# POWER.net
KiCad netlist of a schematic drawn in Altium Designer
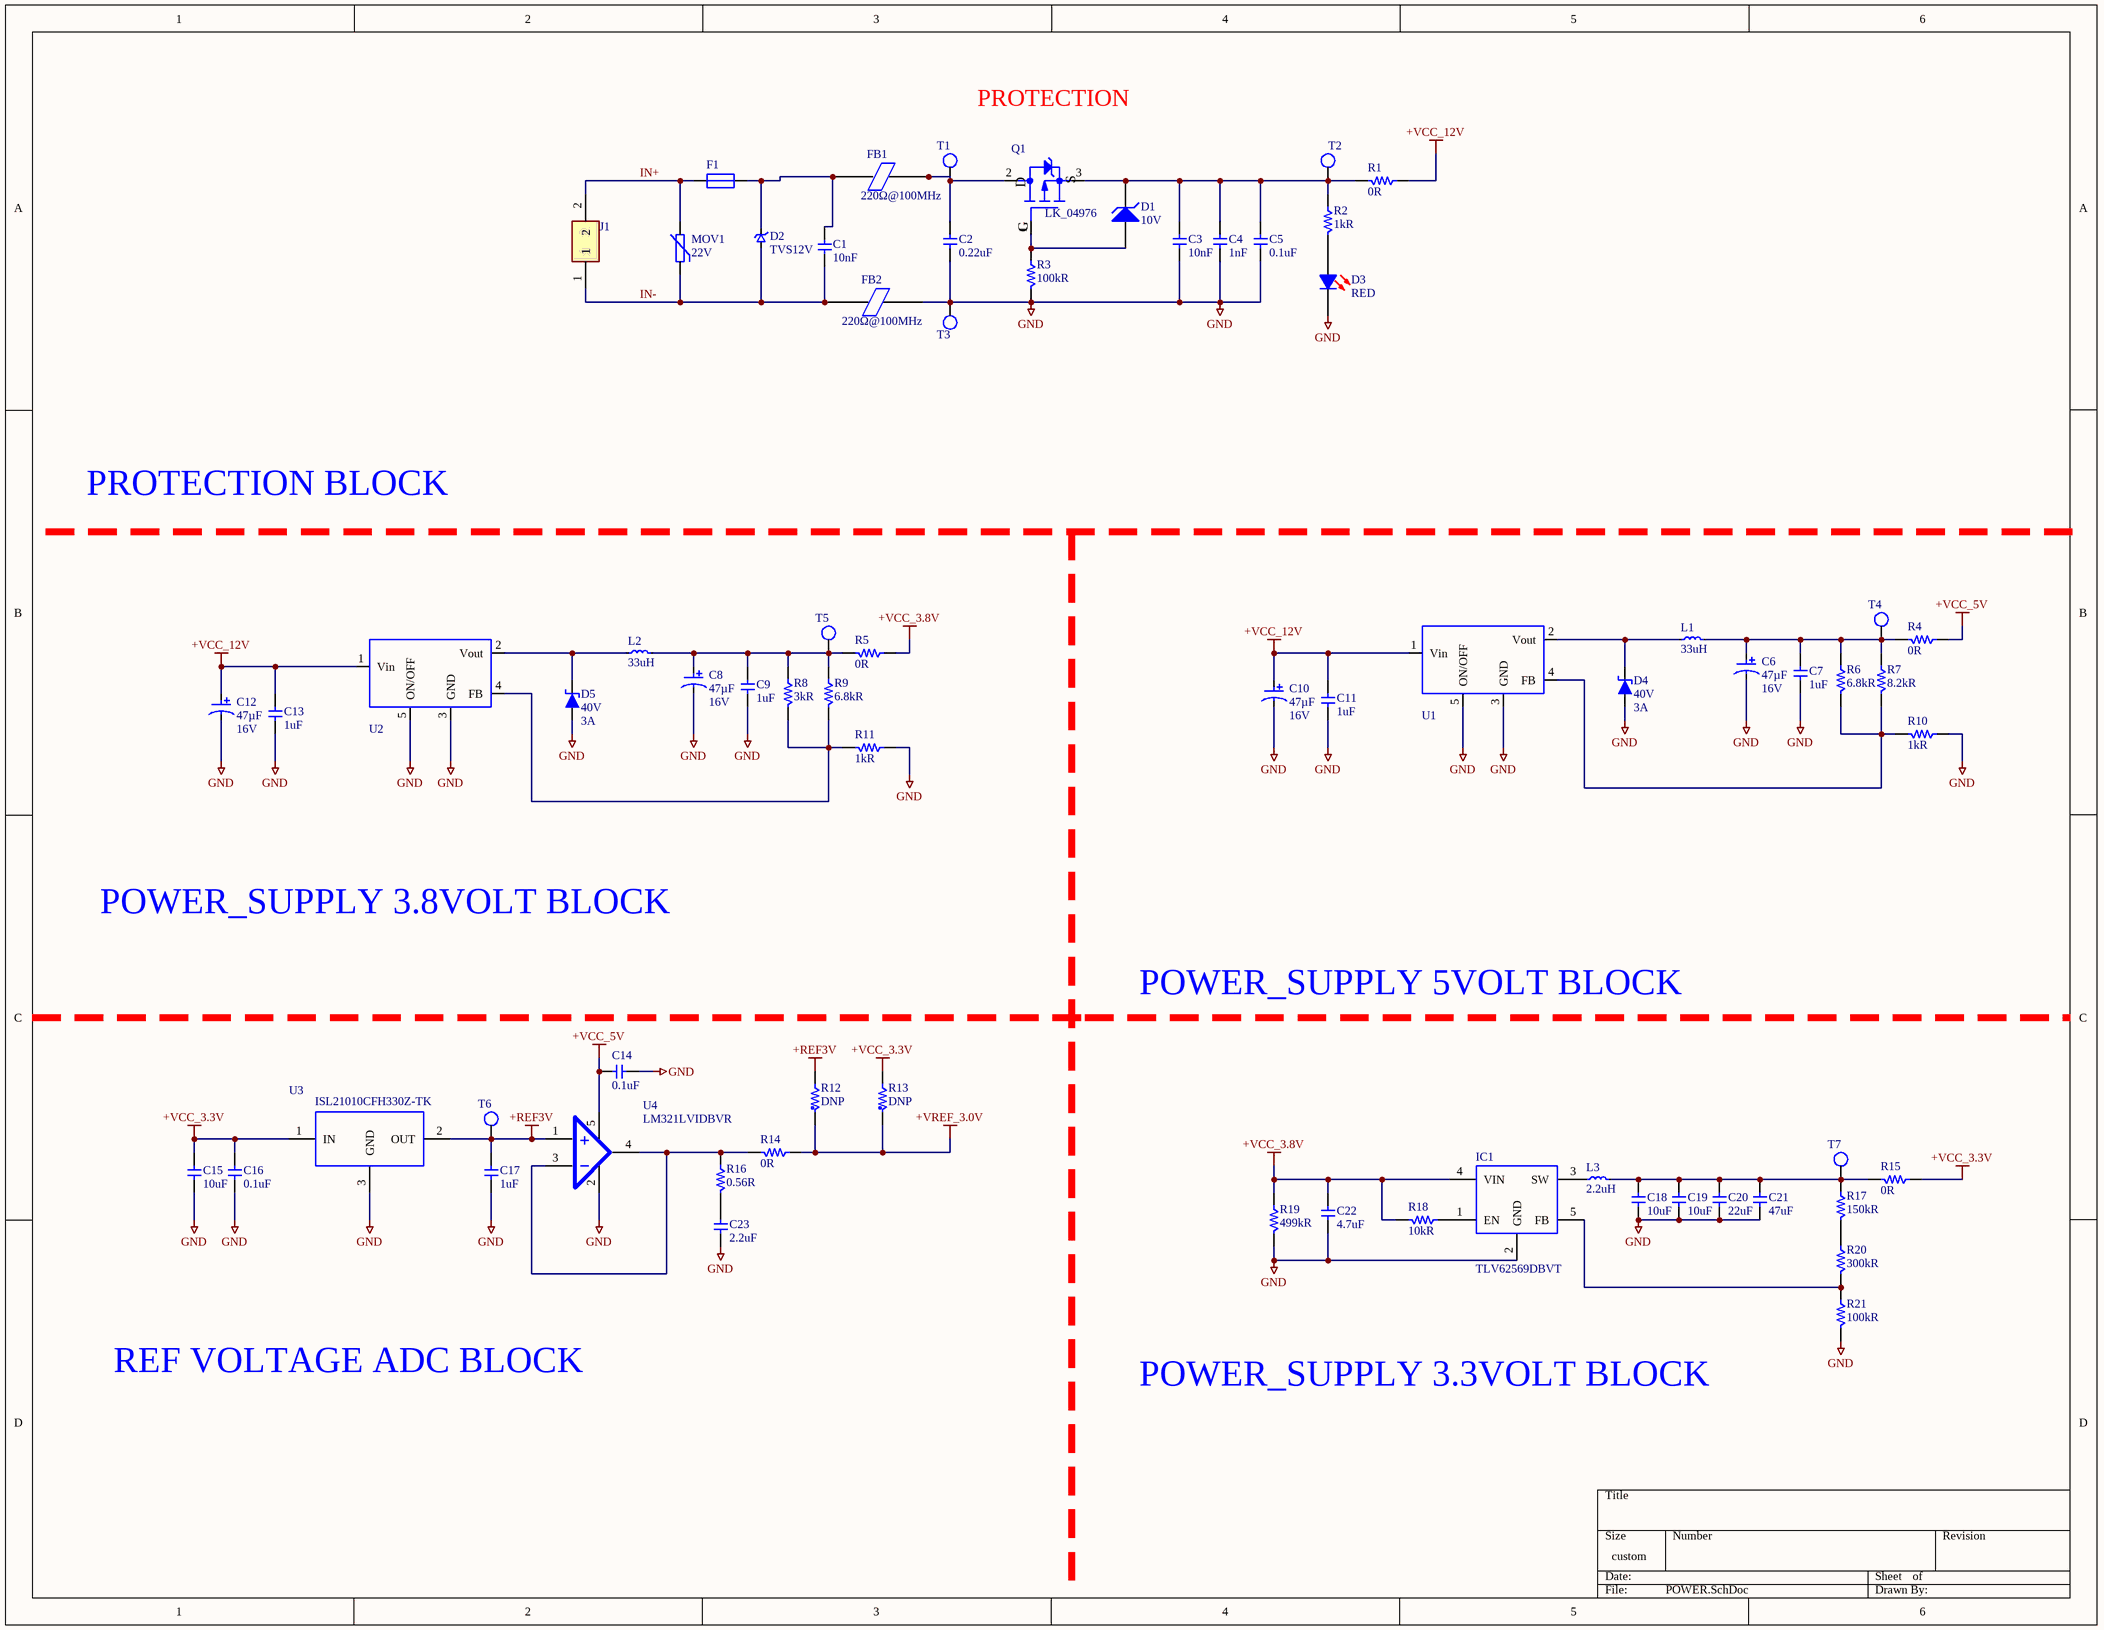
[diagram p0: POWER.SchDoc]

(export (version "E")
  (design (tool "Eeschema 10.0.6"))
  (components
    (comp (ref "C1")
      (value "10nF")
      (footprint "CAP 0402 (1005)")
      (description "50V 10nF ±5% 0402 Multilayer Ceramic Capacitors MLCC - SMD/SMT ROHS")
      (fields
        (field (name "MANUFACTURER") "FH (Guangdong Fenghua Advanced Tech)")
        (field (name "MANUFACTURER PART NUMBER") "0402B103J500NT")
      )
      (libsource (lib "BSR NODE_V2.0 LIB") (part "CAP0402 10nF 50V"))
    )
    (comp (ref "C2")
      (value "0.22uF")
      (footprint "CAP 0402 (1005)")
      (description "35V 0.22uF X5R ±10% 0402 Multilayer Ceramic Capacitors MLCC - SMD/SMT ROHS")
      (fields
        (field (name "MANUFACTURER") "Murata Electronics")
        (field (name "MANUFACTURER PART NUMBER") "GRT155R6YA224KE01D")
      )
      (libsource (lib "BSR NODE_V2.0 LIB") (part "CAP0402 0.22uF 35V"))
    )
    (comp (ref "C3")
      (value "10nF")
      (footprint "CAP 0402 (1005)")
      (description "50V 10nF ±5% 0402 Multilayer Ceramic Capacitors MLCC - SMD/SMT ROHS")
      (fields
        (field (name "MANUFACTURER") "FH (Guangdong Fenghua Advanced Tech)")
        (field (name "MANUFACTURER PART NUMBER") "0402B103J500NT")
      )
      (libsource (lib "BSR NODE_V2.0 LIB") (part "CAP0402 10nF 50V"))
    )
    (comp (ref "C4")
      (value "1nF")
      (footprint "CAP 0402 (1005)")
      (description "50V 1nF ±5% 0402 Multilayer Ceramic Capacitors MLCC - SMD/SMT ROHS")
      (fields
        (field (name "MANUFACTURER") "Murata Electronics")
        (field (name "MANUFACTURER PART NUMBER") "GCM1555C1H102JA16J")
      )
      (libsource (lib "BSR NODE_V2.0 LIB") (part "CAP0402 1nF 50V"))
    )
    (comp (ref "C5")
      (value "0.1uF")
      (footprint "CAP 0402 (1005)")
      (description "50V 100nF ±10% 0402 Multilayer Ceramic Capacitors MLCC - SMD/SMT ROHS")
      (fields
        (field (name "MANUFACTURER") "Samwha Capacitor")
        (field (name "MANUFACTURER PART NUMBER") "CS1005X7R104K500NR")
      )
      (libsource (lib "BSR NODE_V2.0 LIB") (part "CAP0402 0.1uF 50V"))
    )
    (comp (ref "C6")
      (value "TAJC476M016RNJ")
      (footprint "CAP TANTA 2312")
      (description "CAP TANTA 47UF 16V 2312 20%")
      (fields
        (field (name "MANUFACTURER") "AVX Corporation")
        (field (name "TOLERANCE") "±20%")
        (field (name "CAPACITANCE") "47µF")
        (field (name "VOLTAGE - RATED") "16V")
      )
      (libsource (lib "BSR") (part "CAP TANTA 47UF 16V 2312 20%"))
    )
    (comp (ref "C7")
      (value "1uF")
      (footprint "CAP 0402 (1005)")
      (description "25V 1uF ±10% 0402 Multilayer Ceramic Capacitors MLCC - SMD/SMT ROHS")
      (fields
        (field (name "MANUFACTURER") "FH (Guangdong Fenghua Advanced Tech)")
        (field (name "MANUFACTURER PART NUMBER") "0402X105K250NT")
      )
      (libsource (lib "BSR NODE_V2.0 LIB") (part "CAP0402 1uF 25V"))
    )
    (comp (ref "C8")
      (value "TAJC476M016RNJ")
      (footprint "CAP TANTA 2312")
      (description "CAP TANTA 47UF 16V 2312 20%")
      (fields
        (field (name "MANUFACTURER") "AVX Corporation")
        (field (name "TOLERANCE") "±20%")
        (field (name "CAPACITANCE") "47µF")
        (field (name "VOLTAGE - RATED") "16V")
      )
      (libsource (lib "BSR") (part "CAP TANTA 47UF 16V 2312 20%"))
    )
    (comp (ref "C9")
      (value "1uF")
      (footprint "CAP 0402 (1005)")
      (description "25V 1uF ±10% 0402 Multilayer Ceramic Capacitors MLCC - SMD/SMT ROHS")
      (fields
        (field (name "MANUFACTURER") "FH (Guangdong Fenghua Advanced Tech)")
        (field (name "MANUFACTURER PART NUMBER") "0402X105K250NT")
      )
      (libsource (lib "BSR NODE_V2.0 LIB") (part "CAP0402 1uF 25V"))
    )
    (comp (ref "C10")
      (value "TAJC476M016RNJ")
      (footprint "CAP TANTA 2312")
      (description "CAP TANTA 47UF 16V 2312 20%")
      (fields
        (field (name "MANUFACTURER") "AVX Corporation")
        (field (name "TOLERANCE") "±20%")
        (field (name "CAPACITANCE") "47µF")
        (field (name "VOLTAGE - RATED") "16V")
      )
      (libsource (lib "BSR") (part "CAP TANTA 47UF 16V 2312 20%"))
    )
    (comp (ref "C11")
      (value "1uF")
      (footprint "CAP 0402 (1005)")
      (description "25V 1uF ±10% 0402 Multilayer Ceramic Capacitors MLCC - SMD/SMT ROHS")
      (fields
        (field (name "MANUFACTURER") "FH (Guangdong Fenghua Advanced Tech)")
        (field (name "MANUFACTURER PART NUMBER") "0402X105K250NT")
      )
      (libsource (lib "BSR NODE_V2.0 LIB") (part "CAP0402 1uF 25V"))
    )
    (comp (ref "C12")
      (value "TAJC476M016RNJ")
      (footprint "CAP TANTA 2312")
      (description "CAP TANTA 47UF 16V 2312 20%")
      (fields
        (field (name "MANUFACTURER") "AVX Corporation")
        (field (name "TOLERANCE") "±20%")
        (field (name "CAPACITANCE") "47µF")
        (field (name "VOLTAGE - RATED") "16V")
      )
      (libsource (lib "BSR") (part "CAP TANTA 47UF 16V 2312 20%"))
    )
    (comp (ref "C13")
      (value "1uF")
      (footprint "CAP 0402 (1005)")
      (description "25V 1uF ±10% 0402 Multilayer Ceramic Capacitors MLCC - SMD/SMT ROHS")
      (fields
        (field (name "MANUFACTURER") "FH (Guangdong Fenghua Advanced Tech)")
        (field (name "MANUFACTURER PART NUMBER") "0402X105K250NT")
      )
      (libsource (lib "BSR NODE_V2.0 LIB") (part "CAP0402 1uF 25V"))
    )
    (comp (ref "C14")
      (value "0.1uF")
      (footprint "CAP 0402 (1005)")
      (description "50V 100nF ±10% 0402 Multilayer Ceramic Capacitors MLCC - SMD/SMT ROHS")
      (fields
        (field (name "MANUFACTURER") "Samwha Capacitor")
        (field (name "MANUFACTURER PART NUMBER") "CS1005X7R104K500NR")
      )
      (libsource (lib "BSR NODE_V2.0 LIB") (part "CAP0402 0.1uF 50V"))
    )
    (comp (ref "C15")
      (value "10uF")
      (footprint "CAP 0603 (1608)")
      (description "25V 10uF X5R ±20% 0603 Multilayer Ceramic Capacitors MLCC - SMD/SMT ROHS")
      (fields
        (field (name "MANUFACTURER") "Chinocera")
        (field (name "MANUFACTURER PART NUMBER") "HGC0603R5106M250NTHJ")
      )
      (libsource (lib "BSR NODE_V2.0 LIB") (part "CAP0603 10uF 25V"))
    )
    (comp (ref "C16")
      (value "0.1uF")
      (footprint "CAP 0402 (1005)")
      (description "50V 100nF ±10% 0402 Multilayer Ceramic Capacitors MLCC - SMD/SMT ROHS")
      (fields
        (field (name "MANUFACTURER") "Samwha Capacitor")
        (field (name "MANUFACTURER PART NUMBER") "CS1005X7R104K500NR")
      )
      (libsource (lib "BSR NODE_V2.0 LIB") (part "CAP0402 0.1uF 50V"))
    )
    (comp (ref "C17")
      (value "1uF")
      (footprint "CAP 0402 (1005)")
      (description "25V 1uF ±10% 0402 Multilayer Ceramic Capacitors MLCC - SMD/SMT ROHS")
      (fields
        (field (name "MANUFACTURER") "FH (Guangdong Fenghua Advanced Tech)")
        (field (name "MANUFACTURER PART NUMBER") "0402X105K250NT")
      )
      (libsource (lib "BSR NODE_V2.0 LIB") (part "CAP0402 1uF 25V"))
    )
    (comp (ref "C18")
      (value "10uF")
      (footprint "CAP 0603 (1608)")
      (description "25V 10uF X5R ±20% 0603 Multilayer Ceramic Capacitors MLCC - SMD/SMT ROHS")
      (fields
        (field (name "MANUFACTURER") "Chinocera")
        (field (name "MANUFACTURER PART NUMBER") "HGC0603R5106M250NTHJ")
      )
      (libsource (lib "BSR NODE_V2.0 LIB") (part "CAP0603 10uF 25V"))
    )
    (comp (ref "C19")
      (value "10uF")
      (footprint "CAP 0603 (1608)")
      (description "25V 10uF X5R ±20% 0603 Multilayer Ceramic Capacitors MLCC - SMD/SMT ROHS")
      (fields
        (field (name "MANUFACTURER") "Chinocera")
        (field (name "MANUFACTURER PART NUMBER") "HGC0603R5106M250NTHJ")
      )
      (libsource (lib "BSR NODE_V2.0 LIB") (part "CAP0603 10uF 25V"))
    )
    (comp (ref "C20")
      (value "22uF")
      (footprint "CAP 0805 (2012)")
      (description "25V 22uF X5R ±20% 0805 Multilayer Ceramic Capacitors MLCC - SMD/SMT ROHS")
      (fields
        (field (name "MANUFACTURER") "Murata Electronics")
        (field (name "MANUFACTURER PART NUMBER") "GRM21BR61E226ME44L")
      )
      (libsource (lib "BSR NODE_V2.0 LIB") (part "CAP0805 22uF 25V"))
    )
    (comp (ref "C21")
      (value "47uF")
      (footprint "CAP 1206 (3216)")
      (description "47uF ±10% 1206 Multilayer Ceramic Capacitors MLCC - SMD/SMT ROHS")
      (fields
        (field (name "MANUFACTURER") "Murata Electronics")
        (field (name "MANUFACTURER PART NUMBER") "GRM31CC80J476KE01L")
      )
      (libsource (lib "BSR NODE_V2.0 LIB") (part "CAP1206 47uF"))
    )
    (comp (ref "C22")
      (value "4.7uF")
      (footprint "CAP 0402 (1005)")
      (description "25V 4.7uF X5R 0402 Multilayer Ceramic Capacitors MLCC - SMD/SMT ROHS")
      (fields
        (field (name "MANUFACTURER") "Murata Electronics")
        (field (name "MANUFACTURER PART NUMBER") "GRM155R61E475ME15D")
      )
      (libsource (lib "BSR NODE_V2.0 LIB") (part "CAP0402 4.7uF 25V"))
    )
    (comp (ref "C23")
      (value "2.2uF")
      (footprint "CAP 0402 (1005)")
      (description "35V 2.2uF X5R ±20% 0402 Multilayer Ceramic Capacitors MLCC - SMD/SMT ROHS")
      (fields
        (field (name "MANUFACTURER") "Murata Electronics")
        (field (name "MANUFACTURER PART NUMBER") "GRM155R6YA225ME11D")
      )
      (libsource (lib "BSR NODE_V2.0 LIB") (part "CAP0402 2.2uF 35V"))
    )
    (comp (ref "D1")
      (value "10V")
      (footprint "SOT-323")
      (description "Schottky Diode10V Single 600mV@1A 3A SOD-323 Schottky Barrier Diodes (SBD) ROHS")
      (fields (field (name "MANUFACTURER") "High Diode") (field (name "MANUFACTURER PART NUMBER") "BAT60B"))
      (libsource (lib "BSR NODE_V2.0 LIB") (part "BAT60B"))
    )
    (comp (ref "D2")
      (value "TVS12V")
      (footprint "TVS SMAj12A")
      (description "TVS DIODE 12VWM 19.9VC DO214AC")
      (fields
        (field (name "MANUFACTURER") "Littelfuse Inc.")
        (field (name "MANUFACTURER PART NUMBER") "SMAJ12A")
      )
      (libsource (lib "BSR") (part "TVS DIODE SMAJ12A"))
    )
    (comp (ref "D3")
      (value "RED")
      (footprint "LED 0402 RED")
      (description "Red 0402 Light Emitting Diodes (LED) ROHS")
      (fields
        (field (name "MANUFACTURER") "BrtLed(Bright LED Elec)")
        (field (name "MANUFACTURER PART NUMBER") "BL-HUB37A-AV-TRB")
      )
      (libsource (lib "BSR NODE_V2.0 LIB") (part "LED RED 0402"))
    )
    (comp (ref "D4")
      (value "SS34")
      (footprint "DO-214AC")
      (description "DIO SMD 3A 40V")
      (fields
        (field (name "MANUFACTURER") "Fairchild Semiconductor")
        (field (name "VOLTAGE - DC REVERSE (VR) (MAX)") "40V")
        (field (name "CURRENT - AVERAGE RECTIFIED (IO)") "3A")
      )
      (libsource (lib "BSR") (part "DIO SCHOTTKY 3A 40V"))
    )
    (comp (ref "D5")
      (value "SS34")
      (footprint "DO-214AC")
      (description "DIO SMD 3A 40V")
      (fields
        (field (name "MANUFACTURER") "Fairchild Semiconductor")
        (field (name "VOLTAGE - DC REVERSE (VR) (MAX)") "40V")
        (field (name "CURRENT - AVERAGE RECTIFIED (IO)") "3A")
      )
      (libsource (lib "BSR") (part "DIO SCHOTTKY 3A 40V"))
    )
    (comp (ref "F1")
      (value "MF-NSML260/12-2")
      (footprint "FUSC3216X100N")
      (description "PTC RESET FUSE 12V 2.6A 1206")
      (fields (field (name "MANUFACTURER") "Bourns Inc."))
      (libsource (lib "BSR") (part "MF-NSML260_12-2"))
    )
    (comp (ref "FB1")
      (value "220Ω@100MHz")
      (footprint "FB 0402 (1005)")
      (description "±25% 220Ω@100MHz 0402 Ferrite Beads ROHS")
      (fields
        (field (name "MANUFACTURER") "Cybermax")
        (field (name "MANUFACTURER PART NUMBER") "CMBH1005S221LSP")
      )
      (libsource (lib "BSR NODE_V2.0 LIB") (part "CMBH1005S221LSP"))
    )
    (comp (ref "FB2")
      (value "220Ω@100MHz")
      (footprint "FB 0402 (1005)")
      (description "±25% 220Ω@100MHz 0402 Ferrite Beads ROHS")
      (fields
        (field (name "MANUFACTURER") "Cybermax")
        (field (name "MANUFACTURER PART NUMBER") "CMBH1005S221LSP")
      )
      (libsource (lib "BSR NODE_V2.0 LIB") (part "CMBH1005S221LSP"))
    )
    (comp (ref "IC1")
      (value "TLV62569DBVT")
      (footprint "TLV62569DBVR")
      (description "IC REG BUCK ADJ 2A SOT23-5")
      (fields (field (name "MANUFACTURER") "Texas Instruments"))
      (libsource (lib "BSR") (part "TLV62569DBVR"))
    )
    (comp (ref "J1")
      (value "B2B-XH-2__LF__SN_")
      (footprint "JST_B2B-XH-A(LF)(SN)")
      (description "Connector")
      (fields (field (name "MANUFACTURER_PART_NUMBER") "B2B-XH-2 (LF)(SN)"))
      (libsource (lib "BSR") (part "B2B-XH-2__LF__SN_"))
    )
    (comp (ref "L1")
      (value "33uH")
      (footprint "CDRH127 (12x12x7MM)")
      (description "FIXED IND 33UH 3A 59 MOHM SMD")
      (fields
        (field (name "MANUFACTURER") "Sumida")
        (field (name "MANUFACTURER PART NUMBER") "CDRH125L125NP-330MC")
      )
      (libsource (lib "BSR") (part "IND 33uH 3A 12x12mm"))
    )
    (comp (ref "L2")
      (value "33uH")
      (footprint "CDRH127 (12x12x7MM)")
      (description "FIXED IND 33UH 3A 59 MOHM SMD")
      (fields
        (field (name "MANUFACTURER") "Sumida")
        (field (name "MANUFACTURER PART NUMBER") "CDRH125L125NP-330MC")
      )
      (libsource (lib "BSR") (part "IND 33uH 3A 12x12mm"))
    )
    (comp (ref "L3")
      (value "2.2uH")
      (footprint "IND_4028")
      (description "INDUCTORS FOR POWER CIRCUITS, AU")
      (fields
        (field (name "MANUFACTURER") "TDK")
        (field (name "MANUFACTURER PART NUMBER") "VLS4015CX-2R2M-H")
      )
      (libsource (lib "BSR") (part "IND 2.2uH VLS4015CX-2R2M-H"))
    )
    (comp (ref "MOV1")
      (value "22V")
      (footprint "MOV22")
      (description "VARISTOR 22V 30A 0603")
      (fields
        (field (name "MANUFACTURER") "Bourns Inc.")
        (field (name "MANUFACTURER PART NUMBER") "CG0603MLA-18KE")
      )
      (libsource (lib "BSR") (part "MOV22"))
    )
    (comp (ref "Q1")
      (value "LK_04976")
      (footprint "TO-252")
      (description "AOD4185 TO252 MOSFET P-1CH 40A 40V")
      (libsource (lib "BSR") (part "MOSFET PNP AOD4185 _1"))
    )
    (comp (ref "R1")
      (value "0R")
      (footprint "RES 0603 (1608)")
      (description "0Ω 0603 Chip Resistor - Surface Mount ROHS")
      (fields
        (field (name "MANUFACTURER") "KOA Speer Elec")
        (field (name "MANUFACTURER PART NUMBER") "RK73Z1JTTD")
      )
      (libsource (lib "BSR NODE_V2.0 LIB") (part "RES0603 0R"))
    )
    (comp (ref "R2")
      (value "1kR")
      (footprint "RES 0402 (1005)")
      (description "±5% 1kΩ 0402 Chip Resistor - Surface Mount ROHS")
      (fields (field (name "MANUFACTURER") "VO") (field (name "MANUFACTURER PART NUMBER") "SCR0402J1K"))
      (libsource (lib "BSR NODE_V2.0 LIB") (part "RES0402 1kR 1%"))
    )
    (comp (ref "R3")
      (value "100kR")
      (footprint "RES 0402 (1005)")
      (description "±1% 100kΩ 0402 Chip Resistor - Surface Mount ROHS")
      (fields (field (name "MANUFACTURER") "VO") (field (name "MANUFACTURER PART NUMBER") "SCR0402F100K"))
      (libsource (lib "BSR NODE_V2.0 LIB") (part "RES0402 100k 1%"))
    )
    (comp (ref "R4")
      (value "0R")
      (footprint "RES 0603 (1608)")
      (description "0Ω 0603 Chip Resistor - Surface Mount ROHS")
      (fields
        (field (name "MANUFACTURER") "KOA Speer Elec")
        (field (name "MANUFACTURER PART NUMBER") "RK73Z1JTTD")
      )
      (libsource (lib "BSR NODE_V2.0 LIB") (part "RES0603 0R"))
    )
    (comp (ref "R5")
      (value "0R")
      (footprint "RES 0603 (1608)")
      (description "0Ω 0603 Chip Resistor - Surface Mount ROHS")
      (fields
        (field (name "MANUFACTURER") "KOA Speer Elec")
        (field (name "MANUFACTURER PART NUMBER") "RK73Z1JTTD")
      )
      (libsource (lib "BSR NODE_V2.0 LIB") (part "RES0603 0R"))
    )
    (comp (ref "R6")
      (value "6.8kR")
      (footprint "RES 0402 (1005)")
      (description "±1% 6.8kΩ 0402 Chip Resistor - Surface Mount ROHS")
      (fields (field (name "MANUFACTURER") "VO") (field (name "MANUFACTURER PART NUMBER") "SCR0402F6K8"))
      (libsource (lib "BSR NODE_V2.0 LIB") (part "RES0402 6.8k 1%"))
    )
    (comp (ref "R7")
      (value "8.2kR")
      (footprint "RES 0402 (1005)")
      (description "±1% 5.6kΩ 0402 Chip Resistor - Surface Mount ROHS")
      (fields (field (name "MANUFACTURER") "VO") (field (name "MANUFACTURER PART NUMBER") "SCR0402F5K6"))
      (libsource (lib "BSR NODE_V2.0 LIB") (part "RES0402 5.6k 1%_1"))
    )
    (comp (ref "R8")
      (value "3kR")
      (footprint "RES 0402 (1005)")
      (description "±1% 3kΩ 0402 Chip Resistor - Surface Mount ROHS")
      (fields (field (name "MANUFACTURER") "VO") (field (name "MANUFACTURER PART NUMBER") "SCR0402F3K"))
      (libsource (lib "BSR NODE_V2.0 LIB") (part "RES0402 3kR 1%"))
    )
    (comp (ref "R9")
      (value "6.8kR")
      (footprint "RES 0402 (1005)")
      (description "±1% 6.8kΩ 0402 Chip Resistor - Surface Mount ROHS")
      (fields (field (name "MANUFACTURER") "VO") (field (name "MANUFACTURER PART NUMBER") "SCR0402F6K8"))
      (libsource (lib "BSR NODE_V2.0 LIB") (part "RES0402 6.8k 1%"))
    )
    (comp (ref "R10")
      (value "1kR")
      (footprint "RES 0402 (1005)")
      (description "±5% 1kΩ 0402 Chip Resistor - Surface Mount ROHS")
      (fields (field (name "MANUFACTURER") "VO") (field (name "MANUFACTURER PART NUMBER") "SCR0402J1K"))
      (libsource (lib "BSR NODE_V2.0 LIB") (part "RES0402 1kR 1%"))
    )
    (comp (ref "R11")
      (value "1kR")
      (footprint "RES 0402 (1005)")
      (description "±5% 1kΩ 0402 Chip Resistor - Surface Mount ROHS")
      (fields (field (name "MANUFACTURER") "VO") (field (name "MANUFACTURER PART NUMBER") "SCR0402J1K"))
      (libsource (lib "BSR NODE_V2.0 LIB") (part "RES0402 1kR 1%"))
    )
    (comp (ref "R12")
      (value "DNP")
      (footprint "RES 0603 (1608)")
      (description "Res do not populate")
      (libsource (lib "BSR NODE_V2.0 LIB") (part "RES0603 DNP"))
    )
    (comp (ref "R13")
      (value "DNP")
      (footprint "RES 0603 (1608)")
      (description "Res do not populate")
      (libsource (lib "BSR NODE_V2.0 LIB") (part "RES0603 DNP"))
    )
    (comp (ref "R14")
      (value "0R")
      (footprint "RES 0402 (1005)")
      (description "0Ω 0402 Chip Resistor - Surface Mount ROHS")
      (fields
        (field (name "MANUFACTURER") "KOA Speer Elec")
        (field (name "MANUFACTURER PART NUMBER") "RK73Z1ETTP")
      )
      (libsource (lib "BSR NODE_V2.0 LIB") (part "RES0402 0R"))
    )
    (comp (ref "R15")
      (value "0R")
      (footprint "RES 0603 (1608)")
      (description "0Ω 0603 Chip Resistor - Surface Mount ROHS")
      (fields
        (field (name "MANUFACTURER") "KOA Speer Elec")
        (field (name "MANUFACTURER PART NUMBER") "RK73Z1JTTD")
      )
      (libsource (lib "BSR NODE_V2.0 LIB") (part "RES0603 0R"))
    )
    (comp (ref "R16")
      (value "0.56R")
      (footprint "RES 0402 (1005)")
      (description "±5% 560mΩ 0402 Chip Resistor - Surface Mount ROHS")
      (fields (field (name "MANUFACTURER") "VO") (field (name "MANUFACTURER PART NUMBER") "SCR0402JR560"))
      (libsource (lib "BSR NODE_V2.0 LIB") (part "RES0402 0.56R 5%"))
    )
    (comp (ref "R17")
      (value "150kR")
      (footprint "RES 0402 (1005)")
      (description "±1% 150kΩ 0402 Chip Resistor - Surface Mount ROHS")
      (fields (field (name "MANUFACTURER") "VO") (field (name "MANUFACTURER PART NUMBER") "SCR0402F150K"))
      (libsource (lib "BSR NODE_V2.0 LIB") (part "RES0402 150kR 1%"))
    )
    (comp (ref "R18")
      (value "10kR")
      (footprint "RES 0402 (1005)")
      (description "200mW Thick Film Resistors ±100ppm/℃ ±1% 10kΩ 0402 Chip Resistor - Surface Mount ROHS")
      (fields
        (field (name "MANUFACTURER") "Vishay Intertech")
        (field (name "MANUFACTURER PART NUMBER") "RCS040210K0FKED")
      )
      (libsource (lib "BSR NODE_V2.0 LIB") (part "RES0402 10k 1%"))
    )
    (comp (ref "R19")
      (value "499kR")
      (footprint "RES 0402 (1005)")
      (description "±1% 499kΩ 0402 Chip Resistor - Surface Mount ROHS")
      (fields (field (name "MANUFACTURER") "VO") (field (name "MANUFACTURER PART NUMBER") "SCR0402F499K"))
      (libsource (lib "BSR NODE_V2.0 LIB") (part "RES0402 499k 1%"))
    )
    (comp (ref "R20")
      (value "300kR")
      (footprint "RES 0402 (1005)")
      (description "±1% 300kΩ 0402 Chip Resistor - Surface Mount ROHS")
      (fields (field (name "MANUFACTURER") "VO") (field (name "MANUFACTURER PART NUMBER") "SCR0402F300K"))
      (libsource (lib "BSR NODE_V2.0 LIB") (part "RES0402 300kR 1%"))
    )
    (comp (ref "R21")
      (value "100kR")
      (footprint "RES 0402 (1005)")
      (description "±1% 100kΩ 0402 Chip Resistor - Surface Mount ROHS")
      (fields (field (name "MANUFACTURER") "VO") (field (name "MANUFACTURER PART NUMBER") "SCR0402F100K"))
      (libsource (lib "BSR NODE_V2.0 LIB") (part "RES0402 100k 1%"))
    )
    (comp (ref "T1")
      (value "TEST_POINT")
      (footprint "TEST POINT")
      (libsource (lib "BSR") (part "TEST_POINT"))
    )
    (comp (ref "T2")
      (value "TEST_POINT")
      (footprint "TEST POINT")
      (libsource (lib "BSR") (part "TEST_POINT"))
    )
    (comp (ref "T3")
      (value "TEST_POINT")
      (footprint "TEST POINT")
      (libsource (lib "BSR") (part "TEST_POINT"))
    )
    (comp (ref "T4")
      (value "TEST_POINT")
      (footprint "TEST POINT")
      (libsource (lib "BSR") (part "TEST_POINT"))
    )
    (comp (ref "T5")
      (value "TEST_POINT")
      (footprint "TEST POINT")
      (libsource (lib "BSR") (part "TEST_POINT"))
    )
    (comp (ref "T6")
      (value "TEST_POINT")
      (footprint "TEST POINT")
      (libsource (lib "BSR") (part "TEST_POINT"))
    )
    (comp (ref "T7")
      (value "TEST_POINT")
      (footprint "TEST POINT")
      (libsource (lib "BSR") (part "TEST_POINT"))
    )
    (comp (ref "U1")
      (value "LM2596HVS-ADJ")
      (footprint "TO-263-6")
      (description "TO-263 DC-DC CONVERTERS ROHS")
      (fields (field (name "MANUFACTURER") "TI"))
      (libsource (lib "BSR") (part "IC LM2596HVS-ADJ"))
    )
    (comp (ref "U2")
      (value "LM2596HVS-ADJ")
      (footprint "TO-263-6")
      (description "TO-263 DC-DC CONVERTERS ROHS")
      (fields (field (name "MANUFACTURER") "TI"))
      (libsource (lib "BSR") (part "IC LM2596HVS-ADJ"))
    )
    (comp (ref "U3")
      (value "ISL21010CFH330Z-TK")
      (footprint "SOT-23-3")
      (description "IC VREF SERIES 0.2% SOT23-3")
      (fields (field (name "MANUFACTURER") "Intersil") (field (name "TOLERANCE") "±0.2%"))
      (libsource (lib "BSR") (part "IC ISL21010CFH330Z-TK"))
    )
    (comp (ref "U4")
      (value "LM321LVIDBVR")
      (footprint "SOT-23-5")
      (description "IC OPAMP GP 1 CIRCUIT SOT23-5")
      (fields (field (name "MANUFACTURER") "Texas Instruments"))
      (libsource (lib "BSR") (part "IC OPAM LM321LVIDBVR"))
    )
  )
  (nets
    (net (code "1") (name "+REF3V") (class "Default")
      (node (ref "C17") (pin "1") (pinfunction "1_1") (pintype "passive"))
      (node (ref "R12") (pin "2") (pinfunction "2_2") (pintype "passive"))
      (node (ref "T6") (pin "1") (pinfunction "1_1") (pintype "passive"))
      (node (ref "U3") (pin "2") (pinfunction "OUT_2") (pintype "passive"))
      (node (ref "U4") (pin "1") (pinfunction "1_1") (pintype "passive"))
    )
    (net (code "2") (name "+VCC_3.3V") (class "Default")
      (node (ref "C15") (pin "1") (pinfunction "1_1") (pintype "passive"))
      (node (ref "C16") (pin "1") (pinfunction "1_1") (pintype "passive"))
      (node (ref "R13") (pin "2") (pinfunction "2_2") (pintype "passive"))
      (node (ref "R15") (pin "2") (pinfunction "2_2") (pintype "passive"))
      (node (ref "U3") (pin "1") (pinfunction "IN_1") (pintype "passive"))
    )
    (net (code "3") (name "+VCC_3.8V") (class "Default")
      (node (ref "C22") (pin "1") (pinfunction "1_1") (pintype "passive"))
      (node (ref "IC1") (pin "4") (pinfunction "VIN_4") (pintype "passive"))
      (node (ref "R18") (pin "1") (pinfunction "1_1") (pintype "passive"))
      (node (ref "R19") (pin "2") (pinfunction "2_2") (pintype "passive"))
      (node (ref "R5") (pin "2") (pinfunction "2_2") (pintype "passive"))
    )
    (net (code "4") (name "+VCC_5V") (class "Default")
      (node (ref "C14") (pin "2") (pinfunction "2_2") (pintype "passive"))
      (node (ref "R4") (pin "2") (pinfunction "2_2") (pintype "passive"))
      (node (ref "U4") (pin "5") (pinfunction "5_5") (pintype "passive"))
    )
    (net (code "5") (name "+VCC_12V") (class "Default")
      (node (ref "C10") (pin "2") (pinfunction "+_2") (pintype "passive"))
      (node (ref "C11") (pin "1") (pinfunction "1_1") (pintype "passive"))
      (node (ref "C12") (pin "2") (pinfunction "+_2") (pintype "passive"))
      (node (ref "C13") (pin "1") (pinfunction "1_1") (pintype "passive"))
      (node (ref "R1") (pin "2") (pinfunction "2_2") (pintype "passive"))
      (node (ref "U1") (pin "1") (pinfunction "Vin_1") (pintype "passive"))
      (node (ref "U2") (pin "1") (pinfunction "Vin_1") (pintype "passive"))
    )
    (net (code "6") (name "+VREF_3.0V") (class "Default")
      (node (ref "R12") (pin "1") (pinfunction "1_1") (pintype "passive"))
      (node (ref "R13") (pin "1") (pinfunction "1_1") (pintype "passive"))
      (node (ref "R14") (pin "2") (pinfunction "2_2") (pintype "passive"))
    )
    (net (code "7") (name "/IN+") (class "Default")
      (node (ref "F1") (pin "2") (pinfunction "2_2") (pintype "passive"))
      (node (ref "J1") (pin "2") (pinfunction "2_2") (pintype "passive"))
      (node (ref "MOV1") (pin "1") (pinfunction "1_1") (pintype "passive"))
    )
    (net (code "8") (name "/IN-") (class "Default")
      (node (ref "C1") (pin "2") (pinfunction "2_2") (pintype "passive"))
      (node (ref "D2") (pin "2") (pinfunction "2_2") (pintype "passive"))
      (node (ref "FB2") (pin "1") (pinfunction "1_1") (pintype "passive"))
      (node (ref "J1") (pin "1") (pinfunction "1_1") (pintype "passive"))
      (node (ref "MOV1") (pin "2") (pinfunction "2_2") (pintype "passive"))
    )
    (net (code "9") (name "GND") (class "Default")
      (node (ref "C10") (pin "1") (pinfunction "-_1") (pintype "passive"))
      (node (ref "C11") (pin "2") (pinfunction "2_2") (pintype "passive"))
      (node (ref "C12") (pin "1") (pinfunction "-_1") (pintype "passive"))
      (node (ref "C13") (pin "2") (pinfunction "2_2") (pintype "passive"))
      (node (ref "C14") (pin "1") (pinfunction "1_1") (pintype "passive"))
      (node (ref "C15") (pin "2") (pinfunction "2_2") (pintype "passive"))
      (node (ref "C16") (pin "2") (pinfunction "2_2") (pintype "passive"))
      (node (ref "C17") (pin "2") (pinfunction "2_2") (pintype "passive"))
      (node (ref "C18") (pin "2") (pinfunction "2_2") (pintype "passive"))
      (node (ref "C19") (pin "2") (pinfunction "2_2") (pintype "passive"))
      (node (ref "C2") (pin "2") (pinfunction "2_2") (pintype "passive"))
      (node (ref "C20") (pin "2") (pinfunction "2_2") (pintype "passive"))
      (node (ref "C21") (pin "2") (pinfunction "2_2") (pintype "passive"))
      (node (ref "C22") (pin "2") (pinfunction "2_2") (pintype "passive"))
      (node (ref "C23") (pin "2") (pinfunction "2_2") (pintype "passive"))
      (node (ref "C3") (pin "2") (pinfunction "2_2") (pintype "passive"))
      (node (ref "C4") (pin "2") (pinfunction "2_2") (pintype "passive"))
      (node (ref "C5") (pin "2") (pinfunction "2_2") (pintype "passive"))
      (node (ref "C6") (pin "1") (pinfunction "-_1") (pintype "passive"))
      (node (ref "C7") (pin "2") (pinfunction "2_2") (pintype "passive"))
      (node (ref "C8") (pin "1") (pinfunction "-_1") (pintype "passive"))
      (node (ref "C9") (pin "2") (pinfunction "2_2") (pintype "passive"))
      (node (ref "D3") (pin "2") (pinfunction "K_2") (pintype "passive"))
      (node (ref "D4") (pin "1") (pinfunction "A_1") (pintype "passive"))
      (node (ref "D5") (pin "1") (pinfunction "A_1") (pintype "passive"))
      (node (ref "FB2") (pin "2") (pinfunction "2_2") (pintype "passive"))
      (node (ref "IC1") (pin "2") (pinfunction "GND_2") (pintype "passive"))
      (node (ref "R10") (pin "2") (pinfunction "2_2") (pintype "passive"))
      (node (ref "R11") (pin "2") (pinfunction "2_2") (pintype "passive"))
      (node (ref "R19") (pin "1") (pinfunction "1_1") (pintype "passive"))
      (node (ref "R21") (pin "1") (pinfunction "1_1") (pintype "passive"))
      (node (ref "R3") (pin "1") (pinfunction "1_1") (pintype "passive"))
      (node (ref "T3") (pin "1") (pinfunction "1_1") (pintype "passive"))
      (node (ref "U1") (pin "3") (pinfunction "GND_3") (pintype "passive"))
      (node (ref "U1") (pin "5") (pinfunction "ON/OFF_5") (pintype "passive"))
      (node (ref "U2") (pin "3") (pinfunction "GND_3") (pintype "passive"))
      (node (ref "U2") (pin "5") (pinfunction "ON/OFF_5") (pintype "passive"))
      (node (ref "U3") (pin "3") (pinfunction "GND_3") (pintype "power_in"))
      (node (ref "U4") (pin "2") (pinfunction "2_2") (pintype "passive"))
    )
    (net (code "10") (name "Net-(C1-Pad1)") (class "Default")
      (node (ref "C1") (pin "1") (pinfunction "1_1") (pintype "passive"))
      (node (ref "D2") (pin "1") (pinfunction "1_1") (pintype "passive"))
      (node (ref "F1") (pin "1") (pinfunction "1_1") (pintype "passive"))
      (node (ref "FB1") (pin "1") (pinfunction "1_1") (pintype "passive"))
    )
    (net (code "11") (name "Net-(C6-+)") (class "Default")
      (node (ref "C6") (pin "2") (pinfunction "+_2") (pintype "passive"))
      (node (ref "C7") (pin "1") (pinfunction "1_1") (pintype "passive"))
      (node (ref "L1") (pin "2") (pinfunction "2_2") (pintype "passive"))
      (node (ref "R4") (pin "1") (pinfunction "1_1") (pintype "passive"))
      (node (ref "R6") (pin "2") (pinfunction "2_2") (pintype "passive"))
      (node (ref "R7") (pin "2") (pinfunction "2_2") (pintype "passive"))
      (node (ref "T4") (pin "1") (pinfunction "1_1") (pintype "passive"))
    )
    (net (code "12") (name "Net-(C8-+)") (class "Default")
      (node (ref "C8") (pin "2") (pinfunction "+_2") (pintype "passive"))
      (node (ref "C9") (pin "1") (pinfunction "1_1") (pintype "passive"))
      (node (ref "L2") (pin "2") (pinfunction "2_2") (pintype "passive"))
      (node (ref "R5") (pin "1") (pinfunction "1_1") (pintype "passive"))
      (node (ref "R8") (pin "2") (pinfunction "2_2") (pintype "passive"))
      (node (ref "R9") (pin "2") (pinfunction "2_2") (pintype "passive"))
      (node (ref "T5") (pin "1") (pinfunction "1_1") (pintype "passive"))
    )
    (net (code "13") (name "Net-(C18-Pad1)") (class "Default")
      (node (ref "C18") (pin "1") (pinfunction "1_1") (pintype "passive"))
      (node (ref "C19") (pin "1") (pinfunction "1_1") (pintype "passive"))
      (node (ref "C20") (pin "1") (pinfunction "1_1") (pintype "passive"))
      (node (ref "C21") (pin "1") (pinfunction "1_1") (pintype "passive"))
      (node (ref "L3") (pin "2") (pinfunction "2_2") (pintype "passive"))
      (node (ref "R15") (pin "1") (pinfunction "1_1") (pintype "passive"))
      (node (ref "R17") (pin "2") (pinfunction "2_2") (pintype "passive"))
      (node (ref "T7") (pin "1") (pinfunction "1_1") (pintype "passive"))
    )
    (net (code "14") (name "Net-(C23-Pad1)") (class "Default")
      (node (ref "C23") (pin "1") (pinfunction "1_1") (pintype "passive"))
      (node (ref "R16") (pin "1") (pinfunction "1_1") (pintype "passive"))
    )
    (net (code "15") (name "Net-(D1-A)") (class "Default")
      (node (ref "D1") (pin "2") (pinfunction "A_2") (pintype "passive"))
      (node (ref "Q1") (pin "1") (pinfunction "G_1") (pintype "passive"))
      (node (ref "R3") (pin "2") (pinfunction "2_2") (pintype "passive"))
    )
    (net (code "16") (name "Net-(D1-K)") (class "Default")
      (node (ref "C3") (pin "1") (pinfunction "1_1") (pintype "passive"))
      (node (ref "C4") (pin "1") (pinfunction "1_1") (pintype "passive"))
      (node (ref "C5") (pin "1") (pinfunction "1_1") (pintype "passive"))
      (node (ref "D1") (pin "1") (pinfunction "K_1") (pintype "passive"))
      (node (ref "Q1") (pin "3") (pinfunction "S_3") (pintype "passive"))
      (node (ref "R1") (pin "1") (pinfunction "1_1") (pintype "passive"))
      (node (ref "R2") (pin "2") (pinfunction "2_2") (pintype "passive"))
      (node (ref "T2") (pin "1") (pinfunction "1_1") (pintype "passive"))
    )
    (net (code "17") (name "Net-(D3-A)") (class "Default")
      (node (ref "D3") (pin "1") (pinfunction "A_1") (pintype "passive"))
      (node (ref "R2") (pin "1") (pinfunction "1_1") (pintype "passive"))
    )
    (net (code "18") (name "Net-(D4-K)") (class "Default")
      (node (ref "D4") (pin "2") (pinfunction "K_2") (pintype "passive"))
      (node (ref "L1") (pin "1") (pinfunction "1_1") (pintype "passive"))
      (node (ref "U1") (pin "2") (pinfunction "Vout_2") (pintype "passive"))
    )
    (net (code "19") (name "Net-(D5-K)") (class "Default")
      (node (ref "D5") (pin "2") (pinfunction "K_2") (pintype "passive"))
      (node (ref "L2") (pin "1") (pinfunction "1_1") (pintype "passive"))
      (node (ref "U2") (pin "2") (pinfunction "Vout_2") (pintype "passive"))
    )
    (net (code "20") (name "Net-(IC1-EN)") (class "Default")
      (node (ref "IC1") (pin "1") (pinfunction "EN_1") (pintype "passive"))
      (node (ref "R18") (pin "2") (pinfunction "2_2") (pintype "passive"))
    )
    (net (code "21") (name "Net-(IC1-FB)") (class "Default")
      (node (ref "IC1") (pin "5") (pinfunction "FB_5") (pintype "passive"))
      (node (ref "R20") (pin "1") (pinfunction "1_1") (pintype "passive"))
      (node (ref "R21") (pin "2") (pinfunction "2_2") (pintype "passive"))
    )
    (net (code "22") (name "Net-(IC1-SW)") (class "Default")
      (node (ref "IC1") (pin "3") (pinfunction "SW_3") (pintype "passive"))
      (node (ref "L3") (pin "1") (pinfunction "1_1") (pintype "passive"))
    )
    (net (code "23") (name "Net-(Q1-D)") (class "Default")
      (node (ref "C2") (pin "1") (pinfunction "1_1") (pintype "passive"))
      (node (ref "FB1") (pin "2") (pinfunction "2_2") (pintype "passive"))
      (node (ref "Q1") (pin "2") (pinfunction "D_2") (pintype "passive"))
      (node (ref "T1") (pin "1") (pinfunction "1_1") (pintype "passive"))
    )
    (net (code "24") (name "Net-(R14-Pad1)") (class "Default")
      (node (ref "R14") (pin "1") (pinfunction "1_1") (pintype "passive"))
      (node (ref "R16") (pin "2") (pinfunction "2_2") (pintype "passive"))
      (node (ref "U4") (pin "3") (pinfunction "3_3") (pintype "passive"))
      (node (ref "U4") (pin "4") (pinfunction "4_4") (pintype "passive"))
    )
    (net (code "25") (name "Net-(R17-Pad1)") (class "Default")
      (node (ref "R17") (pin "1") (pinfunction "1_1") (pintype "passive"))
      (node (ref "R20") (pin "2") (pinfunction "2_2") (pintype "passive"))
    )
    (net (code "26") (name "Net-(U1-FB)") (class "Default")
      (node (ref "R10") (pin "1") (pinfunction "1_1") (pintype "passive"))
      (node (ref "R6") (pin "1") (pinfunction "1_1") (pintype "passive"))
      (node (ref "R7") (pin "1") (pinfunction "1_1") (pintype "passive"))
      (node (ref "U1") (pin "4") (pinfunction "FB_4") (pintype "passive"))
    )
    (net (code "27") (name "Net-(U2-FB)") (class "Default")
      (node (ref "R11") (pin "1") (pinfunction "1_1") (pintype "passive"))
      (node (ref "R8") (pin "1") (pinfunction "1_1") (pintype "passive"))
      (node (ref "R9") (pin "1") (pinfunction "1_1") (pintype "passive"))
      (node (ref "U2") (pin "4") (pinfunction "FB_4") (pintype "passive"))
    )
  )
)
